# mkstepper-tmc2660.net
KiCad netlist of a schematic drawn in EAGLE
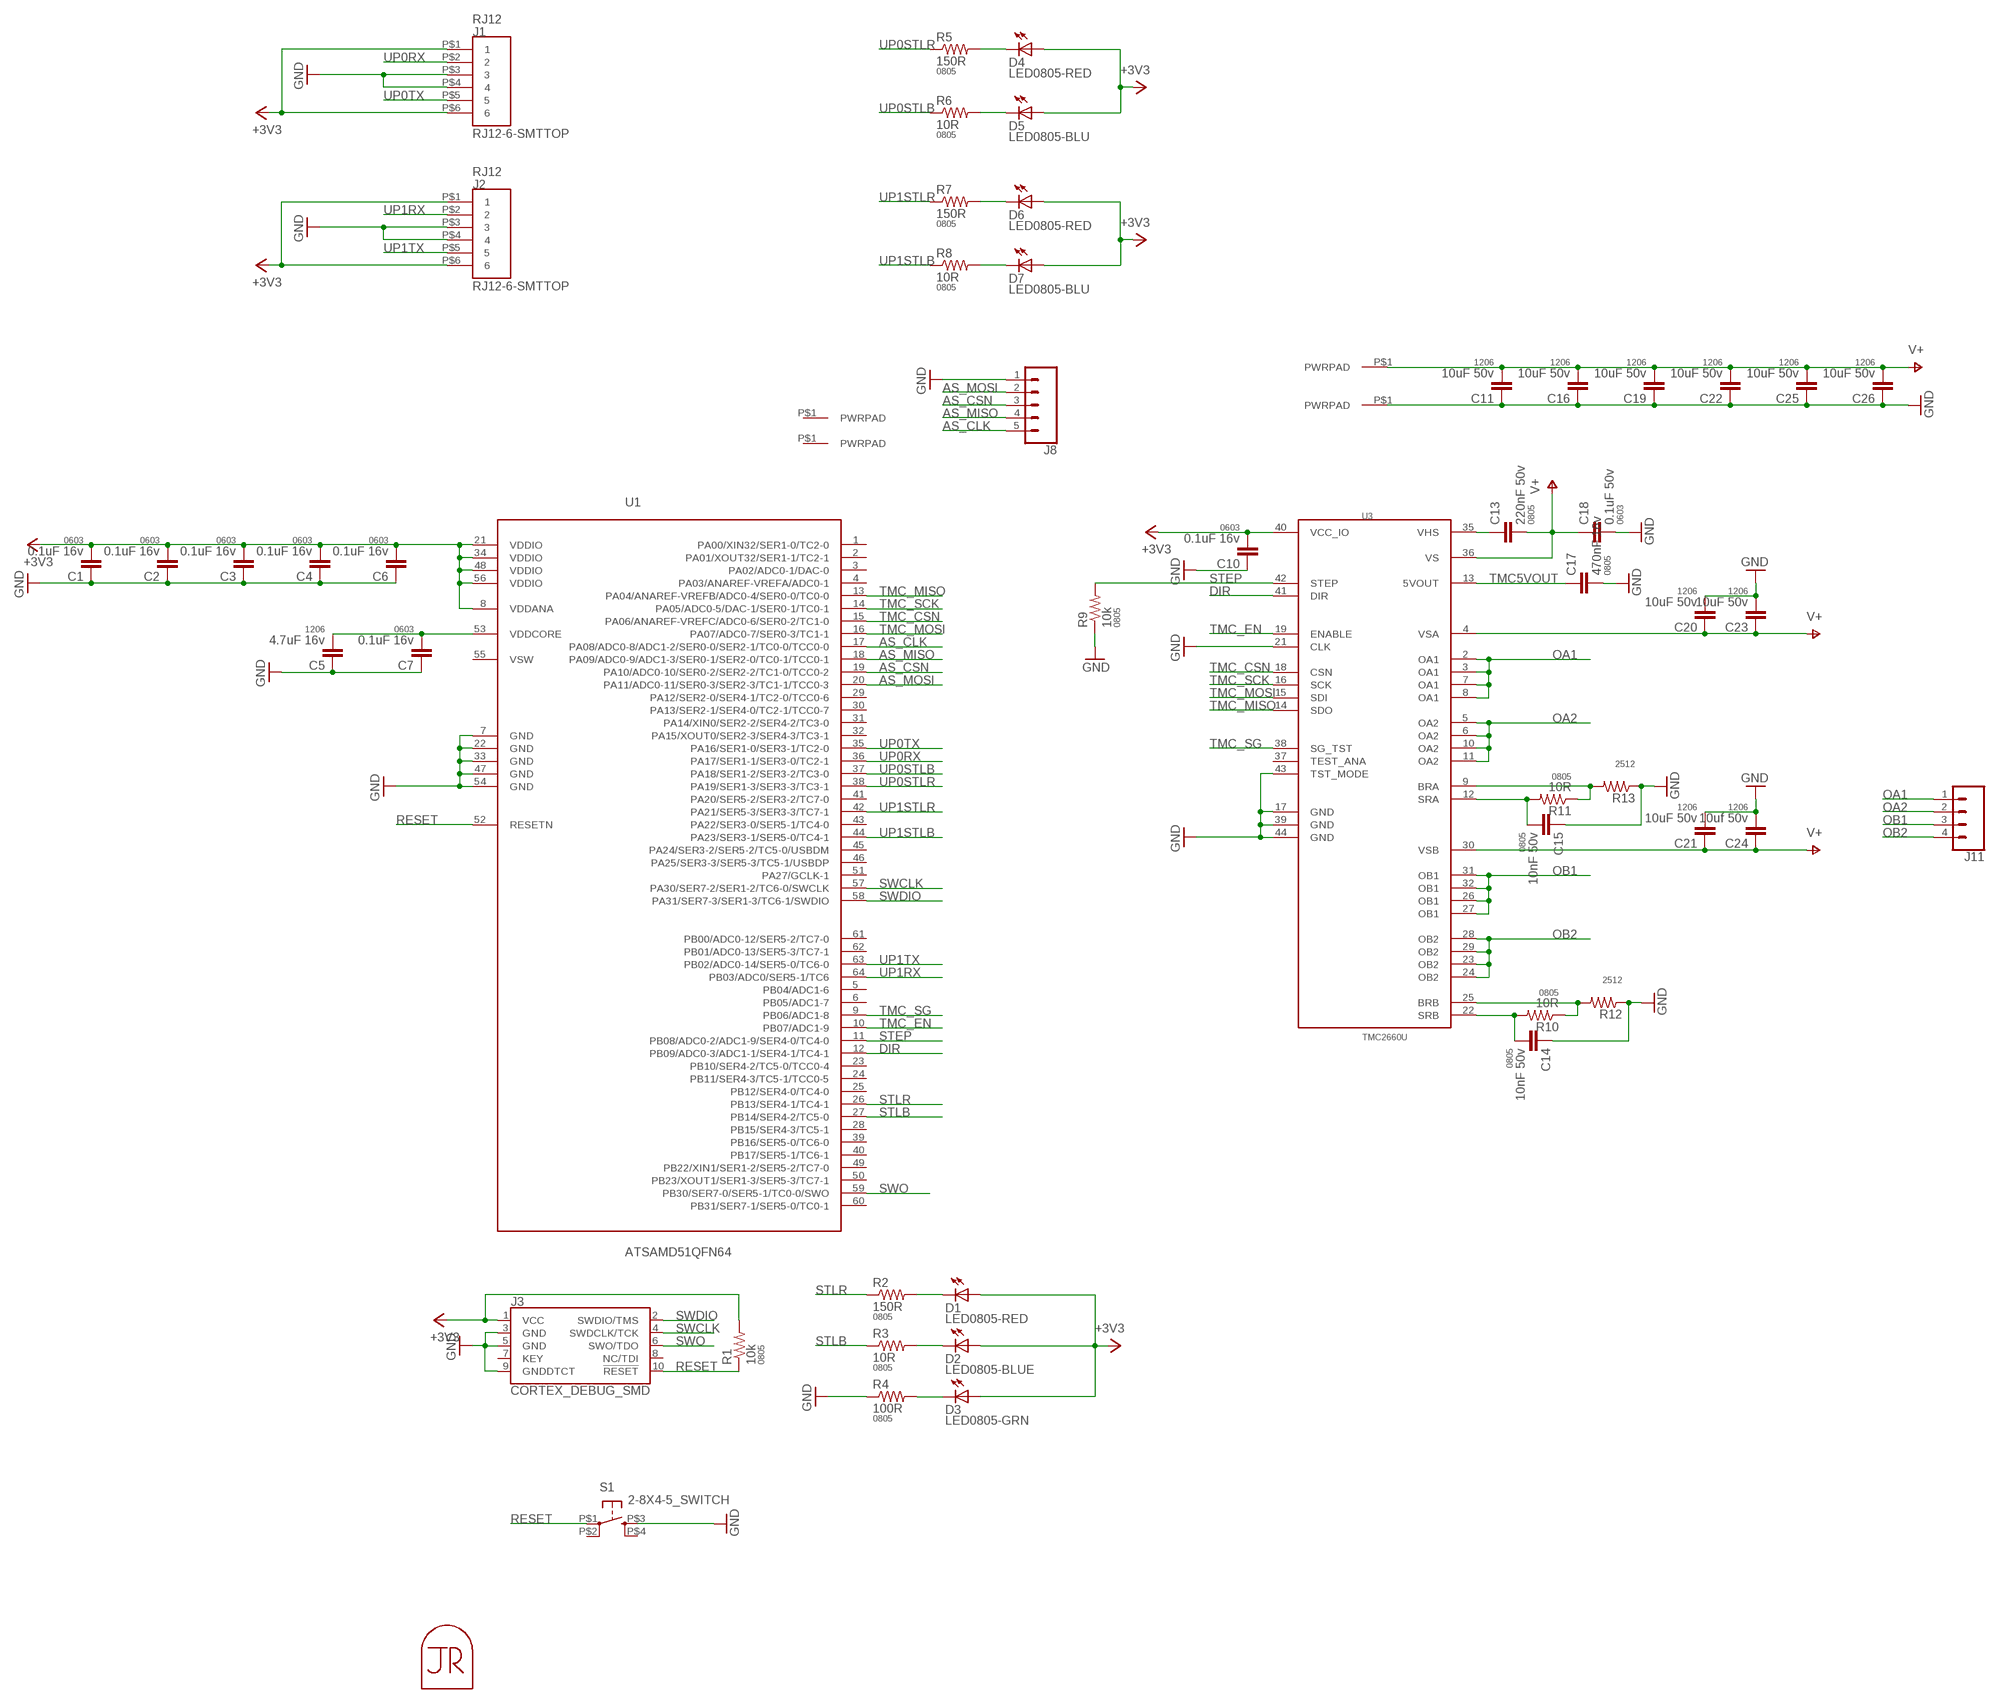
[diagram p0: schematic, sheet 1]

(export (version "E")
  (design (tool "Eeschema 10.0.6"))
  (components
    (comp (ref "C1")
      (value "0.1uF 16v")
      (footprint "eagle-import:0603-CAP")
      (libsource (lib "eagle-import") (part "CAP0603-CAP"))
    )
    (comp (ref "C2")
      (value "0.1uF 16v")
      (footprint "eagle-import:0603-CAP")
      (libsource (lib "eagle-import") (part "CAP0603-CAP"))
    )
    (comp (ref "C3")
      (value "0.1uF 16v")
      (footprint "eagle-import:0603-CAP")
      (libsource (lib "eagle-import") (part "CAP0603-CAP"))
    )
    (comp (ref "C4")
      (value "0.1uF 16v")
      (footprint "eagle-import:0603-CAP")
      (libsource (lib "eagle-import") (part "CAP0603-CAP"))
    )
    (comp (ref "C5")
      (value "4.7uF 16v")
      (footprint "eagle-import:1206")
      (libsource (lib "eagle-import") (part "CAP1206"))
    )
    (comp (ref "C6")
      (value "0.1uF 16v")
      (footprint "eagle-import:0603-CAP")
      (libsource (lib "eagle-import") (part "CAP0603-CAP"))
    )
    (comp (ref "C7")
      (value "0.1uF 16v")
      (footprint "eagle-import:0603-CAP")
      (libsource (lib "eagle-import") (part "CAP0603-CAP"))
    )
    (comp (ref "C10")
      (value "0.1uF 16v")
      (footprint "eagle-import:0603-CAP")
      (libsource (lib "eagle-import") (part "CAP0603-CAP"))
    )
    (comp (ref "C11")
      (value "10uF 50v")
      (footprint "eagle-import:1206")
      (libsource (lib "eagle-import") (part "CAP1206"))
    )
    (comp (ref "C13")
      (value "220nF 50v")
      (footprint "eagle-import:0805")
      (libsource (lib "eagle-import") (part "CAP0805"))
    )
    (comp (ref "C14")
      (value "10nF 50v")
      (footprint "eagle-import:0805")
      (libsource (lib "eagle-import") (part "CAP0805"))
    )
    (comp (ref "C15")
      (value "10nF 50v")
      (footprint "eagle-import:0805")
      (libsource (lib "eagle-import") (part "CAP0805"))
    )
    (comp (ref "C16")
      (value "10uF 50v")
      (footprint "eagle-import:1206")
      (libsource (lib "eagle-import") (part "CAP1206"))
    )
    (comp (ref "C17")
      (value "470nF 16v")
      (footprint "eagle-import:0805")
      (libsource (lib "eagle-import") (part "CAP0805"))
    )
    (comp (ref "C18")
      (value "0.1uF 50v")
      (footprint "eagle-import:0603-CAP")
      (libsource (lib "eagle-import") (part "CAP0603-CAP"))
    )
    (comp (ref "C19")
      (value "10uF 50v")
      (footprint "eagle-import:1206")
      (libsource (lib "eagle-import") (part "CAP1206"))
    )
    (comp (ref "C20")
      (value "10uF 50v")
      (footprint "eagle-import:1206")
      (libsource (lib "eagle-import") (part "CAP1206"))
    )
    (comp (ref "C21")
      (value "10uF 50v")
      (footprint "eagle-import:1206")
      (libsource (lib "eagle-import") (part "CAP1206"))
    )
    (comp (ref "C22")
      (value "10uF 50v")
      (footprint "eagle-import:1206")
      (libsource (lib "eagle-import") (part "CAP1206"))
    )
    (comp (ref "C23")
      (value "10uF 50v")
      (footprint "eagle-import:1206")
      (libsource (lib "eagle-import") (part "CAP1206"))
    )
    (comp (ref "C24")
      (value "10uf 50v")
      (footprint "eagle-import:1206")
      (libsource (lib "eagle-import") (part "CAP1206"))
    )
    (comp (ref "C25")
      (value "10uF 50v")
      (footprint "eagle-import:1206")
      (libsource (lib "eagle-import") (part "CAP1206"))
    )
    (comp (ref "C26")
      (value "10uF 50v")
      (footprint "eagle-import:1206")
      (libsource (lib "eagle-import") (part "CAP1206"))
    )
    (comp (ref "D1")
      (value "LED0805-RED")
      (footprint "eagle-import:LED0805")
      (libsource (lib "eagle-import") (part "LED0805"))
    )
    (comp (ref "D2")
      (value "LED0805-BLUE")
      (footprint "eagle-import:LED0805")
      (libsource (lib "eagle-import") (part "LED0805"))
    )
    (comp (ref "D3")
      (value "LED0805-GRN")
      (footprint "eagle-import:LED0805")
      (libsource (lib "eagle-import") (part "LED0805"))
    )
    (comp (ref "D4")
      (value "LED0805-RED")
      (footprint "eagle-import:LED0805")
      (libsource (lib "eagle-import") (part "LED0805"))
    )
    (comp (ref "D5")
      (value "LED0805-BLU")
      (footprint "eagle-import:LED0805")
      (libsource (lib "eagle-import") (part "LED0805"))
    )
    (comp (ref "D6")
      (value "LED0805-RED")
      (footprint "eagle-import:LED0805")
      (libsource (lib "eagle-import") (part "LED0805"))
    )
    (comp (ref "D7")
      (value "LED0805-BLU")
      (footprint "eagle-import:LED0805")
      (libsource (lib "eagle-import") (part "LED0805"))
    )
    (comp (ref "J1")
      (value "RJ12-6-SMTTOP")
      (footprint "eagle-import:RJ12-6-SMT-TOPENTRY")
      (libsource (lib "eagle-import") (part "RJ12-6-SMTTOP"))
    )
    (comp (ref "J2")
      (value "RJ12-6-SMTTOP")
      (footprint "eagle-import:RJ12-6-SMT-TOPENTRY")
      (libsource (lib "eagle-import") (part "RJ12-6-SMTTOP"))
    )
    (comp (ref "J3")
      (value "CORTEX_DEBUG_SMD")
      (footprint "eagle-import:SAMTECH_FTSH-105-01")
      (libsource (lib "eagle-import") (part "CORTEX_DEBUG_SMD"))
    )
    (comp (ref "J6")
      (value "PWRPADM3")
      (footprint "eagle-import:PWRPAD_3-25MM")
      (libsource (lib "eagle-import") (part "PWRPADM3"))
    )
    (comp (ref "J7")
      (value "PWRPADM3")
      (footprint "eagle-import:PWRPAD_3-25MM")
      (libsource (lib "eagle-import") (part "PWRPADM3"))
    )
    (comp (ref "J8")
      (value "CONN_05NO_SILK")
      (footprint "eagle-import:1X05_NO_SILK")
      (libsource (lib "eagle-import") (part "CONN_05NO_SILK"))
    )
    (comp (ref "J9")
      (value "PWRPAD")
      (footprint "eagle-import:PWRPAD_M3-PEM-MOUNT")
      (libsource (lib "eagle-import") (part "PWRPAD"))
    )
    (comp (ref "J10")
      (value "PWRPAD")
      (footprint "eagle-import:PWRPAD_M3-PEM-MOUNT")
      (libsource (lib "eagle-import") (part "PWRPAD"))
    )
    (comp (ref "J11")
      (value "CONN_04LONGPADS")
      (footprint "eagle-import:1X04_LONGPADS")
      (libsource (lib "eagle-import") (part "CONN_04LONGPADS"))
    )
    (comp (ref "MP1")
      (value "JRTOMBSTONE")
      (footprint "eagle-import:JRTOMBSTONE")
      (libsource (lib "eagle-import") (part "JRTOMBSTONE"))
    )
    (comp (ref "R1")
      (value "10k")
      (footprint "eagle-import:0805")
      (libsource (lib "eagle-import") (part "RESISTOR0805-RES"))
    )
    (comp (ref "R2")
      (value "150R")
      (footprint "eagle-import:0805")
      (libsource (lib "eagle-import") (part "RESISTOR0805-RES"))
    )
    (comp (ref "R3")
      (value "10R")
      (footprint "eagle-import:0805")
      (libsource (lib "eagle-import") (part "RESISTOR0805-RES"))
    )
    (comp (ref "R4")
      (value "100R")
      (footprint "eagle-import:0805")
      (libsource (lib "eagle-import") (part "RESISTOR0805-RES"))
    )
    (comp (ref "R5")
      (value "150R")
      (footprint "eagle-import:0805")
      (libsource (lib "eagle-import") (part "RESISTOR0805-RES"))
    )
    (comp (ref "R6")
      (value "10R")
      (footprint "eagle-import:0805")
      (libsource (lib "eagle-import") (part "RESISTOR0805-RES"))
    )
    (comp (ref "R7")
      (value "150R")
      (footprint "eagle-import:0805")
      (libsource (lib "eagle-import") (part "RESISTOR0805-RES"))
    )
    (comp (ref "R8")
      (value "10R")
      (footprint "eagle-import:0805")
      (libsource (lib "eagle-import") (part "RESISTOR0805-RES"))
    )
    (comp (ref "R9")
      (value "10k")
      (footprint "eagle-import:0805")
      (libsource (lib "eagle-import") (part "RESISTOR0805-RES"))
    )
    (comp (ref "R10")
      (value "10R")
      (footprint "eagle-import:0805")
      (libsource (lib "eagle-import") (part "RESISTOR0805-RES"))
    )
    (comp (ref "R11")
      (value "10R")
      (footprint "eagle-import:0805")
      (libsource (lib "eagle-import") (part "RESISTOR0805-RES"))
    )
    (comp (ref "R12")
      (value "RESISTOR2512")
      (footprint "eagle-import:R2512")
      (libsource (lib "eagle-import") (part "RESISTOR2512"))
    )
    (comp (ref "R13")
      (value "RESISTOR2512")
      (footprint "eagle-import:R2512")
      (libsource (lib "eagle-import") (part "RESISTOR2512"))
    )
    (comp (ref "S1")
      (value "2-8X4-5_SWITCH")
      (footprint "eagle-import:TACT-SWITCH-KMR6")
      (libsource (lib "eagle-import") (part "2-8X4-5_SWITCH"))
    )
    (comp (ref "U1")
      (value "ATSAMD51QFN64")
      (footprint "eagle-import:QFN-64-9X9MM")
      (libsource (lib "eagle-import") (part "ATSAMD51QFN64"))
    )
    (comp (ref "U3")
      (value "TMC2660U")
      (footprint "eagle-import:TQFP44")
      (libsource (lib "eagle-import") (part "TMC2660U"))
    )
  )
  (nets
    (net (code "1") (name "+3V3") (class "Default")
      (node (ref "C1") (pin "2") (pinfunction "2_2") (pintype "passive"))
      (node (ref "C10") (pin "2") (pinfunction "2_2") (pintype "passive"))
      (node (ref "C2") (pin "2") (pinfunction "2_2") (pintype "passive"))
      (node (ref "C3") (pin "2") (pinfunction "2_2") (pintype "passive"))
      (node (ref "C4") (pin "2") (pinfunction "2_2") (pintype "passive"))
      (node (ref "C6") (pin "2") (pinfunction "2_2") (pintype "passive"))
      (node (ref "D1") (pin "1") (pinfunction "A_1") (pintype "passive"))
      (node (ref "D2") (pin "1") (pinfunction "A_1") (pintype "passive"))
      (node (ref "D3") (pin "1") (pinfunction "A_1") (pintype "passive"))
      (node (ref "D4") (pin "1") (pinfunction "A_1") (pintype "passive"))
      (node (ref "D5") (pin "1") (pinfunction "A_1") (pintype "passive"))
      (node (ref "D6") (pin "1") (pinfunction "A_1") (pintype "passive"))
      (node (ref "D7") (pin "1") (pinfunction "A_1") (pintype "passive"))
      (node (ref "J1") (pin "P$1") (pinfunction "1_P$1") (pintype "bidirectional"))
      (node (ref "J1") (pin "P$6") (pinfunction "6_P$6") (pintype "bidirectional"))
      (node (ref "J2") (pin "P$1") (pinfunction "1_P$1") (pintype "bidirectional"))
      (node (ref "J2") (pin "P$6") (pinfunction "6_P$6") (pintype "bidirectional"))
      (node (ref "J3") (pin "1") (pinfunction "VCC_1") (pintype "bidirectional"))
      (node (ref "R1") (pin "2") (pinfunction "2_2") (pintype "passive"))
      (node (ref "U1") (pin "21") (pinfunction "VDDIO_21") (pintype "bidirectional"))
      (node (ref "U1") (pin "34") (pinfunction "VDDIO_34") (pintype "bidirectional"))
      (node (ref "U1") (pin "48") (pinfunction "VDDIO_48") (pintype "bidirectional"))
      (node (ref "U1") (pin "56") (pinfunction "VDDIO_56") (pintype "bidirectional"))
      (node (ref "U1") (pin "8") (pinfunction "VDDANA_8") (pintype "bidirectional"))
      (node (ref "U3") (pin "40") (pinfunction "VCC_IO_40") (pintype "bidirectional"))
    )
    (net (code "2") (name "/AS_CLK") (class "Default")
      (node (ref "J8") (pin "5") (pinfunction "5_5") (pintype "passive"))
      (node (ref "U1") (pin "17") (pinfunction "PA08/ADC0-8/ADC1-2/SER0-0/SER2-1/TC0-0/TCC0-0_17") (pintype "bidirectional"))
    )
    (net (code "3") (name "/AS_CSN") (class "Default")
      (node (ref "J8") (pin "3") (pinfunction "3_3") (pintype "passive"))
      (node (ref "U1") (pin "19") (pinfunction "PA10/ADC0-10/SER0-2/SER2-2/TC1-0/TCC0-2_19") (pintype "bidirectional"))
    )
    (net (code "4") (name "/AS_MISO") (class "Default")
      (node (ref "J8") (pin "4") (pinfunction "4_4") (pintype "passive"))
      (node (ref "U1") (pin "18") (pinfunction "PA09/ADC0-9/ADC1-3/SER0-1/SER2-0/TC0-1/TCC0-1_18") (pintype "bidirectional"))
    )
    (net (code "5") (name "/AS_MOSI") (class "Default")
      (node (ref "J8") (pin "2") (pinfunction "2_2") (pintype "passive"))
      (node (ref "U1") (pin "20") (pinfunction "PA11/ADC0-11/SER0-3/SER2-3/TC1-1/TCC0-3_20") (pintype "bidirectional"))
    )
    (net (code "6") (name "/DIR") (class "Default")
      (node (ref "U1") (pin "12") (pinfunction "PB09/ADC0-3/ADC1-1/SER4-1/TC4-1_12") (pintype "bidirectional"))
      (node (ref "U3") (pin "41") (pinfunction "DIR_41") (pintype "bidirectional"))
    )
    (net (code "7") (name "/OA1") (class "Default")
      (node (ref "J11") (pin "1") (pinfunction "1_1") (pintype "passive"))
      (node (ref "U3") (pin "2") (pinfunction "OA1_2") (pintype "bidirectional"))
      (node (ref "U3") (pin "3") (pinfunction "OA1_3") (pintype "bidirectional"))
      (node (ref "U3") (pin "7") (pinfunction "OA1_7") (pintype "bidirectional"))
      (node (ref "U3") (pin "8") (pinfunction "OA1_8") (pintype "bidirectional"))
    )
    (net (code "8") (name "/OA2") (class "Default")
      (node (ref "J11") (pin "2") (pinfunction "2_2") (pintype "passive"))
      (node (ref "U3") (pin "10") (pinfunction "OA2_10") (pintype "bidirectional"))
      (node (ref "U3") (pin "11") (pinfunction "OA2_11") (pintype "bidirectional"))
      (node (ref "U3") (pin "5") (pinfunction "OA2_5") (pintype "bidirectional"))
      (node (ref "U3") (pin "6") (pinfunction "OA2_6") (pintype "bidirectional"))
    )
    (net (code "9") (name "/OB1") (class "Default")
      (node (ref "J11") (pin "3") (pinfunction "3_3") (pintype "passive"))
      (node (ref "U3") (pin "26") (pinfunction "OB1_26") (pintype "bidirectional"))
      (node (ref "U3") (pin "27") (pinfunction "OB1_27") (pintype "bidirectional"))
      (node (ref "U3") (pin "31") (pinfunction "OB1_31") (pintype "bidirectional"))
      (node (ref "U3") (pin "32") (pinfunction "OB1_32") (pintype "bidirectional"))
    )
    (net (code "10") (name "/OB2") (class "Default")
      (node (ref "J11") (pin "4") (pinfunction "4_4") (pintype "passive"))
      (node (ref "U3") (pin "23") (pinfunction "OB2_23") (pintype "bidirectional"))
      (node (ref "U3") (pin "24") (pinfunction "OB2_24") (pintype "bidirectional"))
      (node (ref "U3") (pin "28") (pinfunction "OB2_28") (pintype "bidirectional"))
      (node (ref "U3") (pin "29") (pinfunction "OB2_29") (pintype "bidirectional"))
    )
    (net (code "11") (name "/RESET") (class "Default")
      (node (ref "J3") (pin "10") (pinfunction "~{RESET}_10") (pintype "bidirectional"))
      (node (ref "R1") (pin "1") (pinfunction "1_1") (pintype "passive"))
      (node (ref "S1") (pin "P$1") (pinfunction "P_P$1") (pintype "passive"))
      (node (ref "U1") (pin "52") (pinfunction "RESETN_52") (pintype "bidirectional"))
    )
    (net (code "12") (name "/STEP") (class "Default")
      (node (ref "R9") (pin "2") (pinfunction "2_2") (pintype "passive"))
      (node (ref "U1") (pin "11") (pinfunction "PB08/ADC0-2/ADC1-9/SER4-0/TC4-0_11") (pintype "bidirectional"))
      (node (ref "U3") (pin "42") (pinfunction "STEP_42") (pintype "bidirectional"))
    )
    (net (code "13") (name "/STLB") (class "Default")
      (node (ref "R3") (pin "1") (pinfunction "1_1") (pintype "passive"))
      (node (ref "U1") (pin "27") (pinfunction "PB14/SER4-2/TC5-0_27") (pintype "bidirectional"))
    )
    (net (code "14") (name "/STLR") (class "Default")
      (node (ref "R2") (pin "1") (pinfunction "1_1") (pintype "passive"))
      (node (ref "U1") (pin "26") (pinfunction "PB13/SER4-1/TC4-1_26") (pintype "bidirectional"))
    )
    (net (code "15") (name "/SWCLK") (class "Default")
      (node (ref "J3") (pin "4") (pinfunction "SWDCLK/TCK_4") (pintype "bidirectional"))
      (node (ref "U1") (pin "57") (pinfunction "PA30/SER7-2/SER1-2/TC6-0/SWCLK_57") (pintype "bidirectional"))
    )
    (net (code "16") (name "/SWDIO") (class "Default")
      (node (ref "J3") (pin "2") (pinfunction "SWDIO/TMS_2") (pintype "bidirectional"))
      (node (ref "U1") (pin "58") (pinfunction "PA31/SER7-3/SER1-3/TC6-1/SWDIO_58") (pintype "bidirectional"))
    )
    (net (code "17") (name "/SWO") (class "Default")
      (node (ref "J3") (pin "6") (pinfunction "SWO/TDO_6") (pintype "bidirectional"))
      (node (ref "U1") (pin "59") (pinfunction "PB30/SER7-0/SER5-1/TC0-0/SWO_59") (pintype "bidirectional"))
    )
    (net (code "18") (name "/TMC5VOUT") (class "Default")
      (node (ref "C17") (pin "1") (pinfunction "1_1") (pintype "passive"))
      (node (ref "U3") (pin "13") (pinfunction "5VOUT_13") (pintype "bidirectional"))
    )
    (net (code "19") (name "/TMC_CSN") (class "Default")
      (node (ref "U1") (pin "15") (pinfunction "PA06/ANAREF-VREFC/ADC0-6/SER0-2/TC1-0_15") (pintype "bidirectional"))
      (node (ref "U3") (pin "18") (pinfunction "CSN_18") (pintype "bidirectional"))
    )
    (net (code "20") (name "/TMC_EN") (class "Default")
      (node (ref "U1") (pin "10") (pinfunction "PB07/ADC1-9_10") (pintype "bidirectional"))
      (node (ref "U3") (pin "19") (pinfunction "ENABLE_19") (pintype "bidirectional"))
    )
    (net (code "21") (name "/TMC_MISO") (class "Default")
      (node (ref "U1") (pin "13") (pinfunction "PA04/ANAREF-VREFB/ADC0-4/SER0-0/TC0-0_13") (pintype "bidirectional"))
      (node (ref "U3") (pin "14") (pinfunction "SDO_14") (pintype "bidirectional"))
    )
    (net (code "22") (name "/TMC_MOSI") (class "Default")
      (node (ref "U1") (pin "16") (pinfunction "PA07/ADC0-7/SER0-3/TC1-1_16") (pintype "bidirectional"))
      (node (ref "U3") (pin "15") (pinfunction "SDI_15") (pintype "bidirectional"))
    )
    (net (code "23") (name "/TMC_SCK") (class "Default")
      (node (ref "U1") (pin "14") (pinfunction "PA05/ADC0-5/DAC-1/SER0-1/TC0-1_14") (pintype "bidirectional"))
      (node (ref "U3") (pin "16") (pinfunction "SCK_16") (pintype "bidirectional"))
    )
    (net (code "24") (name "/TMC_SG") (class "Default")
      (node (ref "U1") (pin "9") (pinfunction "PB06/ADC1-8_9") (pintype "bidirectional"))
      (node (ref "U3") (pin "38") (pinfunction "SG_TST_38") (pintype "bidirectional"))
    )
    (net (code "25") (name "/UP0RX") (class "Default")
      (node (ref "J1") (pin "P$2") (pinfunction "2_P$2") (pintype "bidirectional"))
      (node (ref "U1") (pin "36") (pinfunction "PA17/SER1-1/SER3-0/TC2-1_36") (pintype "bidirectional"))
    )
    (net (code "26") (name "/UP0STLB") (class "Default")
      (node (ref "R6") (pin "1") (pinfunction "1_1") (pintype "passive"))
      (node (ref "U1") (pin "37") (pinfunction "PA18/SER1-2/SER3-2/TC3-0_37") (pintype "bidirectional"))
    )
    (net (code "27") (name "/UP0STLR") (class "Default")
      (node (ref "R5") (pin "1") (pinfunction "1_1") (pintype "passive"))
      (node (ref "U1") (pin "38") (pinfunction "PA19/SER1-3/SER3-3/TC3-1_38") (pintype "bidirectional"))
    )
    (net (code "28") (name "/UP0TX") (class "Default")
      (node (ref "J1") (pin "P$5") (pinfunction "5_P$5") (pintype "bidirectional"))
      (node (ref "U1") (pin "35") (pinfunction "PA16/SER1-0/SER3-1/TC2-0_35") (pintype "bidirectional"))
    )
    (net (code "29") (name "/UP1RX") (class "Default")
      (node (ref "J2") (pin "P$2") (pinfunction "2_P$2") (pintype "bidirectional"))
      (node (ref "U1") (pin "64") (pinfunction "PB03/ADC0/SER5-1/TC6_64") (pintype "bidirectional"))
    )
    (net (code "30") (name "/UP1STLB") (class "Default")
      (node (ref "R8") (pin "1") (pinfunction "1_1") (pintype "passive"))
      (node (ref "U1") (pin "44") (pinfunction "PA23/SER3-1/SER5-0/TC4-1_44") (pintype "bidirectional"))
    )
    (net (code "31") (name "/UP1STLR") (class "Default")
      (node (ref "R7") (pin "1") (pinfunction "1_1") (pintype "passive"))
      (node (ref "U1") (pin "42") (pinfunction "PA21/SER5-3/SER3-3/TC7-1_42") (pintype "bidirectional"))
    )
    (net (code "32") (name "/UP1TX") (class "Default")
      (node (ref "J2") (pin "P$5") (pinfunction "5_P$5") (pintype "bidirectional"))
      (node (ref "U1") (pin "63") (pinfunction "PB02/ADC0-14/SER5-0/TC6-0_63") (pintype "bidirectional"))
    )
    (net (code "33") (name "GND") (class "Default")
      (node (ref "C1") (pin "1") (pinfunction "1_1") (pintype "passive"))
      (node (ref "C10") (pin "1") (pinfunction "1_1") (pintype "passive"))
      (node (ref "C11") (pin "1") (pinfunction "1_1") (pintype "passive"))
      (node (ref "C14") (pin "1") (pinfunction "1_1") (pintype "passive"))
      (node (ref "C15") (pin "1") (pinfunction "1_1") (pintype "passive"))
      (node (ref "C16") (pin "1") (pinfunction "1_1") (pintype "passive"))
      (node (ref "C17") (pin "2") (pinfunction "2_2") (pintype "passive"))
      (node (ref "C18") (pin "2") (pinfunction "2_2") (pintype "passive"))
      (node (ref "C19") (pin "1") (pinfunction "1_1") (pintype "passive"))
      (node (ref "C2") (pin "1") (pinfunction "1_1") (pintype "passive"))
      (node (ref "C20") (pin "2") (pinfunction "2_2") (pintype "passive"))
      (node (ref "C21") (pin "2") (pinfunction "2_2") (pintype "passive"))
      (node (ref "C22") (pin "1") (pinfunction "1_1") (pintype "passive"))
      (node (ref "C23") (pin "2") (pinfunction "2_2") (pintype "passive"))
      (node (ref "C24") (pin "2") (pinfunction "2_2") (pintype "passive"))
      (node (ref "C25") (pin "1") (pinfunction "1_1") (pintype "passive"))
      (node (ref "C26") (pin "1") (pinfunction "1_1") (pintype "passive"))
      (node (ref "C3") (pin "1") (pinfunction "1_1") (pintype "passive"))
      (node (ref "C4") (pin "1") (pinfunction "1_1") (pintype "passive"))
      (node (ref "C5") (pin "1") (pinfunction "1_1") (pintype "passive"))
      (node (ref "C6") (pin "1") (pinfunction "1_1") (pintype "passive"))
      (node (ref "C7") (pin "1") (pinfunction "1_1") (pintype "passive"))
      (node (ref "J1") (pin "P$3") (pinfunction "3_P$3") (pintype "bidirectional"))
      (node (ref "J1") (pin "P$4") (pinfunction "4_P$4") (pintype "bidirectional"))
      (node (ref "J10") (pin "P$1") (pinfunction "PWRPAD_P$1") (pintype "bidirectional"))
      (node (ref "J2") (pin "P$3") (pinfunction "3_P$3") (pintype "bidirectional"))
      (node (ref "J2") (pin "P$4") (pinfunction "4_P$4") (pintype "bidirectional"))
      (node (ref "J3") (pin "3") (pinfunction "GND_3") (pintype "bidirectional"))
      (node (ref "J3") (pin "5") (pinfunction "GND_5") (pintype "bidirectional"))
      (node (ref "J3") (pin "9") (pinfunction "GNDDTCT_9") (pintype "bidirectional"))
      (node (ref "J8") (pin "1") (pinfunction "1_1") (pintype "passive"))
      (node (ref "R12") (pin "1") (pinfunction "1_1") (pintype "passive"))
      (node (ref "R13") (pin "1") (pinfunction "1_1") (pintype "passive"))
      (node (ref "R4") (pin "1") (pinfunction "1_1") (pintype "passive"))
      (node (ref "R9") (pin "1") (pinfunction "1_1") (pintype "passive"))
      (node (ref "S1") (pin "P$3") (pinfunction "S_P$3") (pintype "passive"))
      (node (ref "U1") (pin "22") (pinfunction "GND_22") (pintype "bidirectional"))
      (node (ref "U1") (pin "33") (pinfunction "GND_33") (pintype "bidirectional"))
      (node (ref "U1") (pin "47") (pinfunction "GND_47") (pintype "bidirectional"))
      (node (ref "U1") (pin "54") (pinfunction "GND_54") (pintype "bidirectional"))
      (node (ref "U1") (pin "7") (pinfunction "GND_7") (pintype "bidirectional"))
      (node (ref "U3") (pin "17") (pinfunction "GND_17") (pintype "bidirectional"))
      (node (ref "U3") (pin "21") (pinfunction "CLK_21") (pintype "bidirectional"))
      (node (ref "U3") (pin "39") (pinfunction "GND_39") (pintype "bidirectional"))
      (node (ref "U3") (pin "43") (pinfunction "TST_MODE_43") (pintype "bidirectional"))
      (node (ref "U3") (pin "44") (pinfunction "GND_44") (pintype "bidirectional"))
    )
    (net (code "34") (name "Net-(D1-C)") (class "Default")
      (node (ref "D1") (pin "2") (pinfunction "C_2") (pintype "passive"))
      (node (ref "R2") (pin "2") (pinfunction "2_2") (pintype "passive"))
    )
    (net (code "35") (name "Net-(D2-C)") (class "Default")
      (node (ref "D2") (pin "2") (pinfunction "C_2") (pintype "passive"))
      (node (ref "R3") (pin "2") (pinfunction "2_2") (pintype "passive"))
    )
    (net (code "36") (name "Net-(D3-C)") (class "Default")
      (node (ref "D3") (pin "2") (pinfunction "C_2") (pintype "passive"))
      (node (ref "R4") (pin "2") (pinfunction "2_2") (pintype "passive"))
    )
    (net (code "37") (name "Net-(D4-C)") (class "Default")
      (node (ref "D4") (pin "2") (pinfunction "C_2") (pintype "passive"))
      (node (ref "R5") (pin "2") (pinfunction "2_2") (pintype "passive"))
    )
    (net (code "38") (name "Net-(D5-C)") (class "Default")
      (node (ref "D5") (pin "2") (pinfunction "C_2") (pintype "passive"))
      (node (ref "R6") (pin "2") (pinfunction "2_2") (pintype "passive"))
    )
    (net (code "39") (name "Net-(D6-C)") (class "Default")
      (node (ref "D6") (pin "2") (pinfunction "C_2") (pintype "passive"))
      (node (ref "R7") (pin "2") (pinfunction "2_2") (pintype "passive"))
    )
    (net (code "40") (name "Net-(D7-C)") (class "Default")
      (node (ref "D7") (pin "2") (pinfunction "C_2") (pintype "passive"))
      (node (ref "R8") (pin "2") (pinfunction "2_2") (pintype "passive"))
    )
    (net (code "41") (name "Net-(U1-VDDCORE)") (class "Default")
      (node (ref "C5") (pin "2") (pinfunction "2_2") (pintype "passive"))
      (node (ref "C7") (pin "2") (pinfunction "2_2") (pintype "passive"))
      (node (ref "U1") (pin "53") (pinfunction "VDDCORE_53") (pintype "bidirectional"))
    )
    (net (code "42") (name "Net-(U3-BRA)") (class "Default")
      (node (ref "R11") (pin "1") (pinfunction "1_1") (pintype "passive"))
      (node (ref "R13") (pin "2") (pinfunction "2_2") (pintype "passive"))
      (node (ref "U3") (pin "9") (pinfunction "BRA_9") (pintype "bidirectional"))
    )
    (net (code "43") (name "Net-(U3-BRB)") (class "Default")
      (node (ref "R10") (pin "1") (pinfunction "1_1") (pintype "passive"))
      (node (ref "R12") (pin "2") (pinfunction "2_2") (pintype "passive"))
      (node (ref "U3") (pin "25") (pinfunction "BRB_25") (pintype "bidirectional"))
    )
    (net (code "44") (name "Net-(U3-SRA)") (class "Default")
      (node (ref "C15") (pin "2") (pinfunction "2_2") (pintype "passive"))
      (node (ref "R11") (pin "2") (pinfunction "2_2") (pintype "passive"))
      (node (ref "U3") (pin "12") (pinfunction "SRA_12") (pintype "bidirectional"))
    )
    (net (code "45") (name "Net-(U3-SRB)") (class "Default")
      (node (ref "C14") (pin "2") (pinfunction "2_2") (pintype "passive"))
      (node (ref "R10") (pin "2") (pinfunction "2_2") (pintype "passive"))
      (node (ref "U3") (pin "22") (pinfunction "SRB_22") (pintype "bidirectional"))
    )
    (net (code "46") (name "Net-(U3-VHS)") (class "Default")
      (node (ref "C13") (pin "1") (pinfunction "1_1") (pintype "passive"))
      (node (ref "U3") (pin "35") (pinfunction "VHS_35") (pintype "bidirectional"))
    )
    (net (code "47") (name "V+") (class "Default")
      (node (ref "C11") (pin "2") (pinfunction "2_2") (pintype "passive"))
      (node (ref "C13") (pin "2") (pinfunction "2_2") (pintype "passive"))
      (node (ref "C16") (pin "2") (pinfunction "2_2") (pintype "passive"))
      (node (ref "C18") (pin "1") (pinfunction "1_1") (pintype "passive"))
      (node (ref "C19") (pin "2") (pinfunction "2_2") (pintype "passive"))
      (node (ref "C20") (pin "1") (pinfunction "1_1") (pintype "passive"))
      (node (ref "C21") (pin "1") (pinfunction "1_1") (pintype "passive"))
      (node (ref "C22") (pin "2") (pinfunction "2_2") (pintype "passive"))
      (node (ref "C23") (pin "1") (pinfunction "1_1") (pintype "passive"))
      (node (ref "C24") (pin "1") (pinfunction "1_1") (pintype "passive"))
      (node (ref "C25") (pin "2") (pinfunction "2_2") (pintype "passive"))
      (node (ref "C26") (pin "2") (pinfunction "2_2") (pintype "passive"))
      (node (ref "J9") (pin "P$1") (pinfunction "PWRPAD_P$1") (pintype "bidirectional"))
      (node (ref "U3") (pin "30") (pinfunction "VSB_30") (pintype "bidirectional"))
      (node (ref "U3") (pin "36") (pinfunction "VS_36") (pintype "bidirectional"))
      (node (ref "U3") (pin "4") (pinfunction "VSA_4") (pintype "bidirectional"))
    )
    (net (code "48") (name "unconnected-(J3-KEY-Pad7)") (class "Default")
      (node (ref "J3") (pin "7") (pinfunction "KEY_7") (pintype "bidirectional"))
    )
    (net (code "49") (name "unconnected-(J3-NC{slash}TDI-Pad8)") (class "Default")
      (node (ref "J3") (pin "8") (pinfunction "NC/TDI_8") (pintype "bidirectional"))
    )
    (net (code "50") (name "unconnected-(J6-PWRPAD-PadP$1)") (class "Default")
      (node (ref "J6") (pin "P$1") (pinfunction "PWRPAD_P$1") (pintype "bidirectional"))
    )
    (net (code "51") (name "unconnected-(J7-PWRPAD-PadP$1)") (class "Default")
      (node (ref "J7") (pin "P$1") (pinfunction "PWRPAD_P$1") (pintype "bidirectional"))
    )
    (net (code "52") (name "unconnected-(S1-P1-PadP$2)") (class "Default")
      (node (ref "S1") (pin "P$2") (pinfunction "P1_P$2") (pintype "passive"))
    )
    (net (code "53") (name "unconnected-(S1-S1-PadP$4)") (class "Default")
      (node (ref "S1") (pin "P$4") (pinfunction "S1_P$4") (pintype "passive"))
    )
    (net (code "54") (name "unconnected-(U1-PA00{slash}XIN32{slash}SER1-0{slash}TC2-0-Pad1)") (class "Default")
      (node (ref "U1") (pin "1") (pinfunction "PA00/XIN32/SER1-0/TC2-0_1") (pintype "bidirectional"))
    )
    (net (code "55") (name "unconnected-(U1-PA01{slash}XOUT32{slash}SER1-1{slash}TC2-1-Pad2)") (class "Default")
      (node (ref "U1") (pin "2") (pinfunction "PA01/XOUT32/SER1-1/TC2-1_2") (pintype "bidirectional"))
    )
    (net (code "56") (name "unconnected-(U1-PA02{slash}ADC0-1{slash}DAC-0-Pad3)") (class "Default")
      (node (ref "U1") (pin "3") (pinfunction "PA02/ADC0-1/DAC-0_3") (pintype "bidirectional"))
    )
    (net (code "57") (name "unconnected-(U1-PA03{slash}ANAREF-VREFA{slash}ADC0-1-Pad4)") (class "Default")
      (node (ref "U1") (pin "4") (pinfunction "PA03/ANAREF-VREFA/ADC0-1_4") (pintype "bidirectional"))
    )
    (net (code "58") (name "unconnected-(U1-PA12{slash}SER2-0{slash}SER4-1{slash}TC2-0{slash}TCC0-6-Pad29)") (class "Default")
      (node (ref "U1") (pin "29") (pinfunction "PA12/SER2-0/SER4-1/TC2-0/TCC0-6_29") (pintype "bidirectional"))
    )
    (net (code "59") (name "unconnected-(U1-PA13{slash}SER2-1{slash}SER4-0{slash}TC2-1{slash}TCC0-7-Pad30)") (class "Default")
      (node (ref "U1") (pin "30") (pinfunction "PA13/SER2-1/SER4-0/TC2-1/TCC0-7_30") (pintype "bidirectional"))
    )
    (net (code "60") (name "unconnected-(U1-PA14{slash}XIN0{slash}SER2-2{slash}SER4-2{slash}TC3-0-Pad31)") (class "Default")
      (node (ref "U1") (pin "31") (pinfunction "PA14/XIN0/SER2-2/SER4-2/TC3-0_31") (pintype "bidirectional"))
    )
    (net (code "61") (name "unconnected-(U1-PA15{slash}XOUT0{slash}SER2-3{slash}SER4-3{slash}TC3-1-Pad32)") (class "Default")
      (node (ref "U1") (pin "32") (pinfunction "PA15/XOUT0/SER2-3/SER4-3/TC3-1_32") (pintype "bidirectional"))
    )
    (net (code "62") (name "unconnected-(U1-PA20{slash}SER5-2{slash}SER3-2{slash}TC7-0-Pad41)") (class "Default")
      (node (ref "U1") (pin "41") (pinfunction "PA20/SER5-2/SER3-2/TC7-0_41") (pintype "bidirectional"))
    )
    (net (code "63") (name "unconnected-(U1-PA22{slash}SER3-0{slash}SER5-1{slash}TC4-0-Pad43)") (class "Default")
      (node (ref "U1") (pin "43") (pinfunction "PA22/SER3-0/SER5-1/TC4-0_43") (pintype "bidirectional"))
    )
    (net (code "64") (name "unconnected-(U1-PA24{slash}SER3-2{slash}SER5-2{slash}TC5-0{slash}USBDM-Pad45)") (class "Default")
      (node (ref "U1") (pin "45") (pinfunction "PA24/SER3-2/SER5-2/TC5-0/USBDM_45") (pintype "bidirectional"))
    )
    (net (code "65") (name "unconnected-(U1-PA25{slash}SER3-3{slash}SER5-3{slash}TC5-1{slash}USBDP-Pad46)") (class "Default")
      (node (ref "U1") (pin "46") (pinfunction "PA25/SER3-3/SER5-3/TC5-1/USBDP_46") (pintype "bidirectional"))
    )
    (net (code "66") (name "unconnected-(U1-PA27{slash}GCLK-1-Pad51)") (class "Default")
      (node (ref "U1") (pin "51") (pinfunction "PA27/GCLK-1_51") (pintype "bidirectional"))
    )
    (net (code "67") (name "unconnected-(U1-PB00{slash}ADC0-12{slash}SER5-2{slash}TC7-0-Pad61)") (class "Default")
      (node (ref "U1") (pin "61") (pinfunction "PB00/ADC0-12/SER5-2/TC7-0_61") (pintype "bidirectional"))
    )
    (net (code "68") (name "unconnected-(U1-PB01{slash}ADC0-13{slash}SER5-3{slash}TC7-1-Pad62)") (class "Default")
      (node (ref "U1") (pin "62") (pinfunction "PB01/ADC0-13/SER5-3/TC7-1_62") (pintype "bidirectional"))
    )
    (net (code "69") (name "unconnected-(U1-PB04{slash}ADC1-6-Pad5)") (class "Default")
      (node (ref "U1") (pin "5") (pinfunction "PB04/ADC1-6_5") (pintype "bidirectional"))
    )
    (net (code "70") (name "unconnected-(U1-PB05{slash}ADC1-7-Pad6)") (class "Default")
      (node (ref "U1") (pin "6") (pinfunction "PB05/ADC1-7_6") (pintype "bidirectional"))
    )
    (net (code "71") (name "unconnected-(U1-PB10{slash}SER4-2{slash}TC5-0{slash}TCC0-4-Pad23)") (class "Default")
      (node (ref "U1") (pin "23") (pinfunction "PB10/SER4-2/TC5-0/TCC0-4_23") (pintype "bidirectional"))
    )
    (net (code "72") (name "unconnected-(U1-PB11{slash}SER4-3{slash}TC5-1{slash}TCC0-5-Pad24)") (class "Default")
      (node (ref "U1") (pin "24") (pinfunction "PB11/SER4-3/TC5-1/TCC0-5_24") (pintype "bidirectional"))
    )
    (net (code "73") (name "unconnected-(U1-PB12{slash}SER4-0{slash}TC4-0-Pad25)") (class "Default")
      (node (ref "U1") (pin "25") (pinfunction "PB12/SER4-0/TC4-0_25") (pintype "bidirectional"))
    )
    (net (code "74") (name "unconnected-(U1-PB15{slash}SER4-3{slash}TC5-1-Pad28)") (class "Default")
      (node (ref "U1") (pin "28") (pinfunction "PB15/SER4-3/TC5-1_28") (pintype "bidirectional"))
    )
    (net (code "75") (name "unconnected-(U1-PB16{slash}SER5-0{slash}TC6-0-Pad39)") (class "Default")
      (node (ref "U1") (pin "39") (pinfunction "PB16/SER5-0/TC6-0_39") (pintype "bidirectional"))
    )
    (net (code "76") (name "unconnected-(U1-PB17{slash}SER5-1{slash}TC6-1-Pad40)") (class "Default")
      (node (ref "U1") (pin "40") (pinfunction "PB17/SER5-1/TC6-1_40") (pintype "bidirectional"))
    )
    (net (code "77") (name "unconnected-(U1-PB22{slash}XIN1{slash}SER1-2{slash}SER5-2{slash}TC7-0-Pad49)") (class "Default")
      (node (ref "U1") (pin "49") (pinfunction "PB22/XIN1/SER1-2/SER5-2/TC7-0_49") (pintype "bidirectional"))
    )
    (net (code "78") (name "unconnected-(U1-PB23{slash}XOUT1{slash}SER1-3{slash}SER5-3{slash}TC7-1-Pad50)") (class "Default")
      (node (ref "U1") (pin "50") (pinfunction "PB23/XOUT1/SER1-3/SER5-3/TC7-1_50") (pintype "bidirectional"))
    )
    (net (code "79") (name "unconnected-(U1-PB31{slash}SER7-1{slash}SER5-0{slash}TC0-1-Pad60)") (class "Default")
      (node (ref "U1") (pin "60") (pinfunction "PB31/SER7-1/SER5-0/TC0-1_60") (pintype "bidirectional"))
    )
    (net (code "80") (name "unconnected-(U1-VSW-Pad55)") (class "Default")
      (node (ref "U1") (pin "55") (pinfunction "VSW_55") (pintype "bidirectional"))
    )
    (net (code "81") (name "unconnected-(U3-TEST_ANA-Pad37)") (class "Default")
      (node (ref "U3") (pin "37") (pinfunction "TEST_ANA_37") (pintype "bidirectional"))
    )
  )
)
